# Interface_Voltage_Sensor_1.net
KiCad netlist of a schematic drawn in Altium Designer
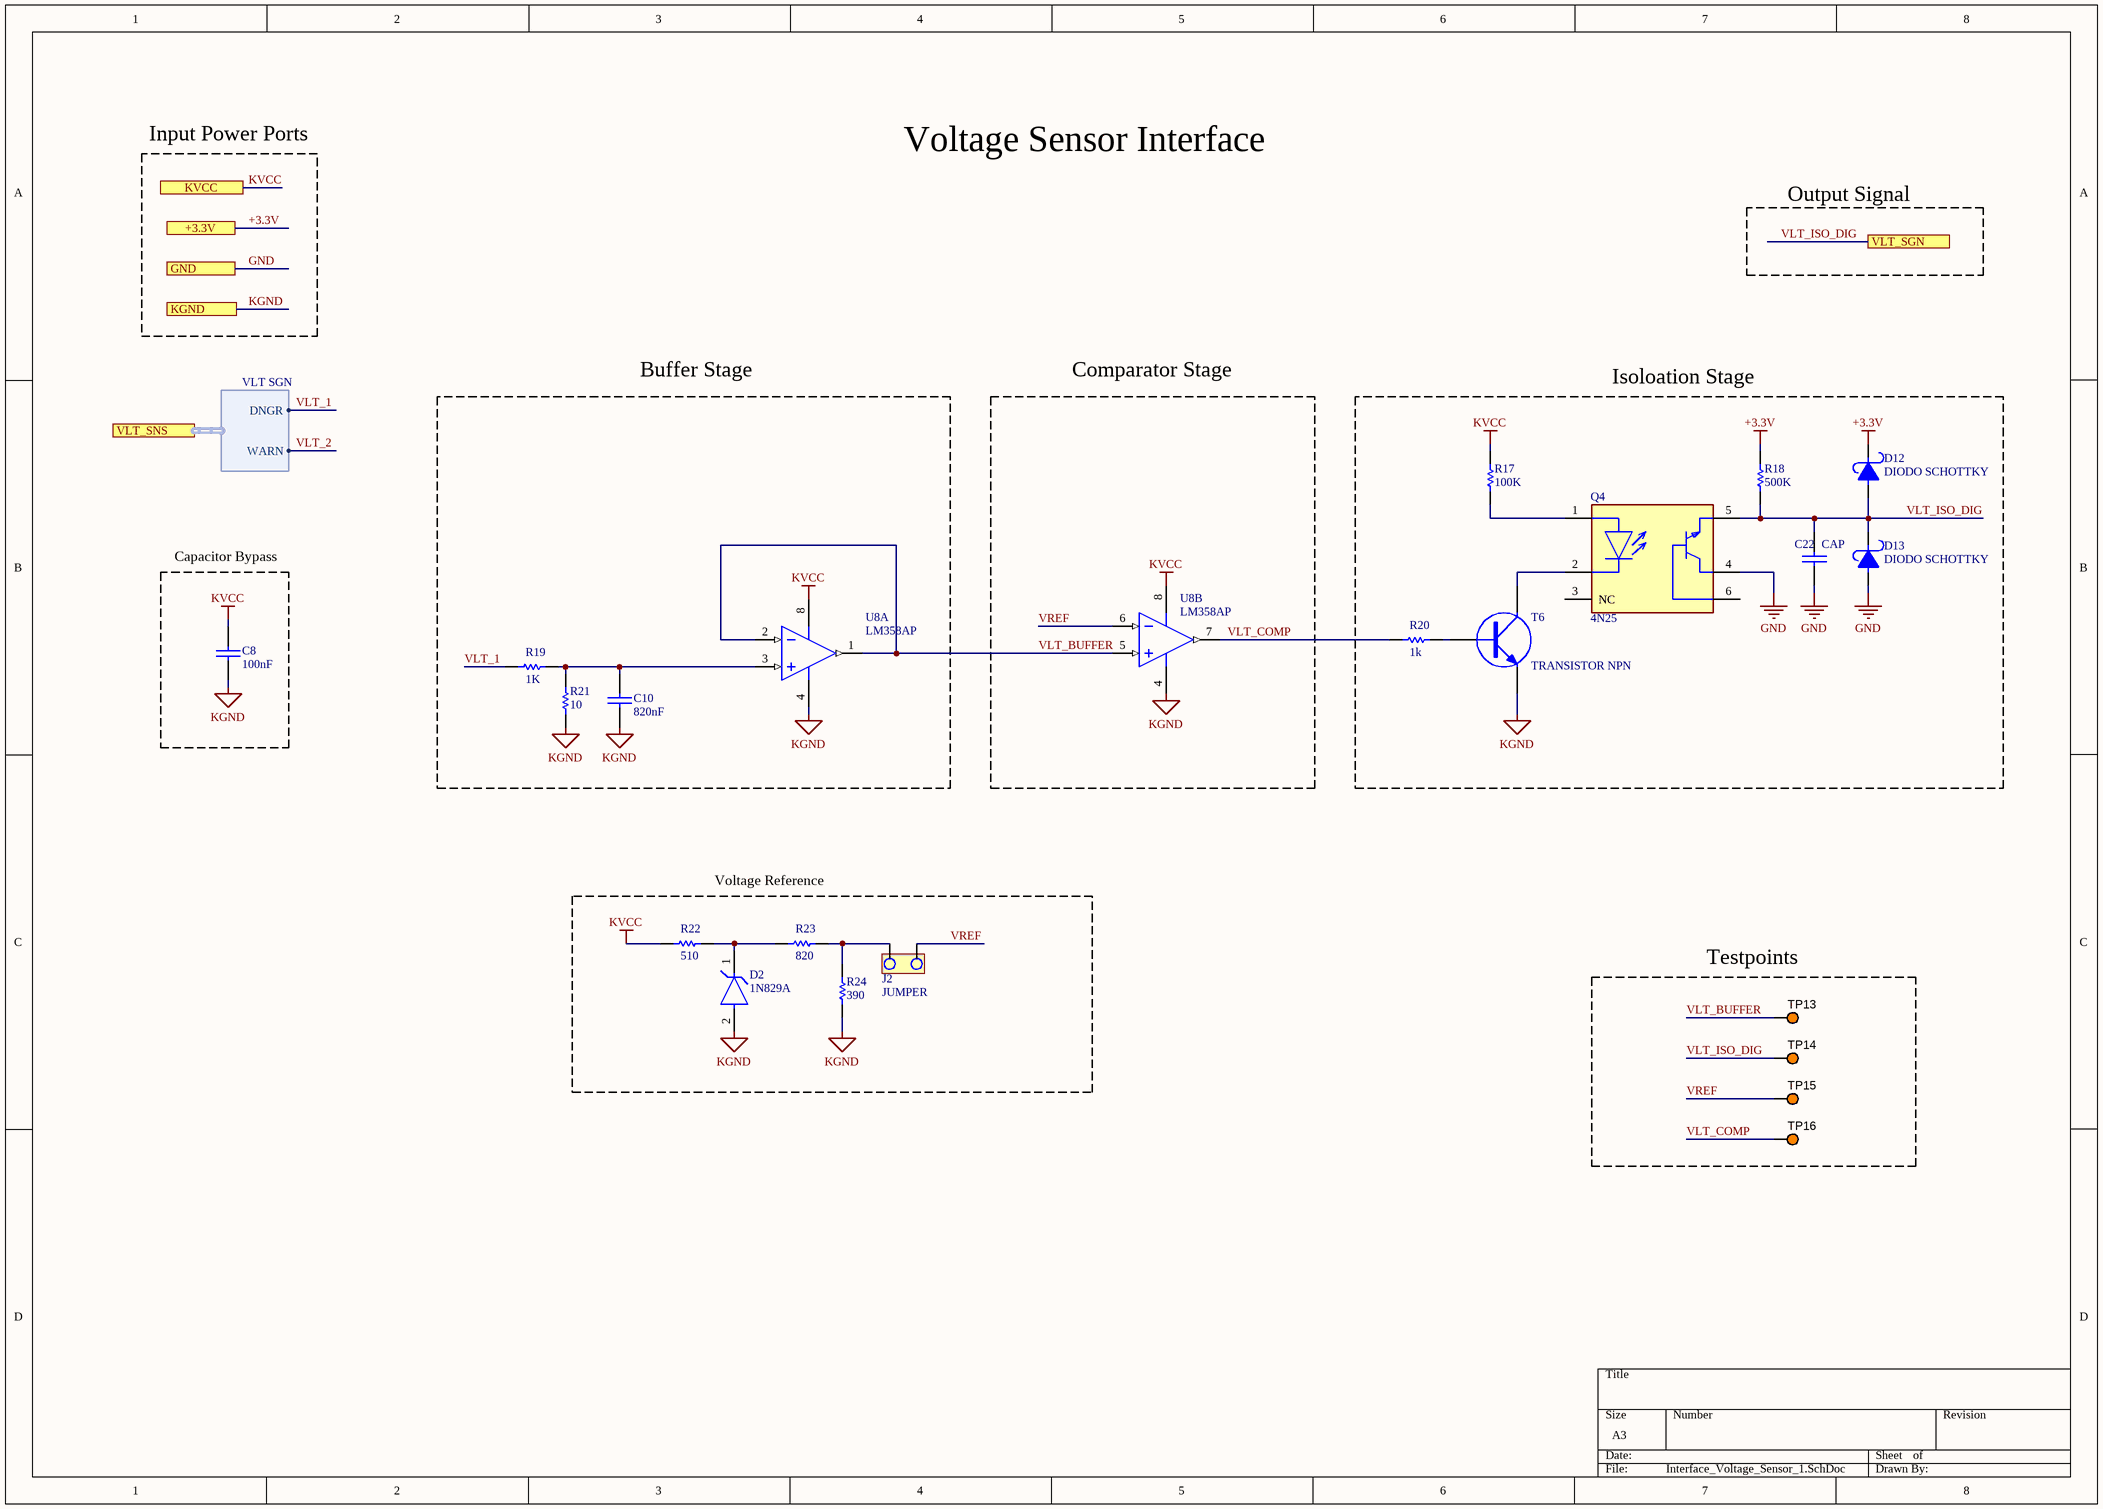
[diagram p0: Interface_Voltage_Sensor_1.SchDoc]

(export (version "E")
  (design (tool "Eeschema 10.0.6"))
  (components
    (comp (ref "C8") (value "100nF") (footprint "CAP200") (libsource (lib "LIBEBAL") (part "CAP")))
    (comp (ref "C10") (value "820nF") (footprint "CAP200") (libsource (lib "LIBEBAL") (part "CAP")))
    (comp (ref "C22") (value "CAP") (footprint "CAP200") (libsource (lib "LIBEBAL") (part "CAP")))
    (comp (ref "D2")
      (value "1N829A")
      (footprint "FP-DO-35-MFG")
      (description "Zener Diode, 6.2V V(Z), 4.84%, 0.5W, Silicon, DO-204AA")
      (libsource (lib "TD") (part "f813f71cba58e380607f5dd3caf9714"))
    )
    (comp (ref "D12")
      (value "DIODO SCHOTTKY")
      (footprint "DO41")
      (libsource (lib "LIBEBAL") (part "DIODO SCHOTTKY"))
    )
    (comp (ref "D13")
      (value "DIODO SCHOTTKY")
      (footprint "DO41")
      (libsource (lib "LIBEBAL") (part "DIODO SCHOTTKY"))
    )
    (comp (ref "J2") (value "JUMPER") (footprint "JUMPER2") (libsource (lib "LIBEBAL") (part "JUMPER")))
    (comp (ref "Q4")
      (value "4N25")
      (footprint "FP-4N25-MFG")
      (description "VISHAY 4N25 Transistor Output Optocoupler, 1 Channel, DIP, 6 Pins, 60 mA, 5 kV, 20 %")
      (libsource (lib "TD") (part "f1df9f29c47de6998195431899ac75d"))
    )
    (comp (ref "R17") (value "100K") (footprint "RES400") (libsource (lib "TD") (part "RES")))
    (comp (ref "R18") (value "500K") (footprint "RES400") (libsource (lib "TD") (part "RES")))
    (comp (ref "R19") (value "1K") (footprint "RES400") (libsource (lib "TD") (part "RES")))
    (comp (ref "R20") (value "1k") (footprint "RES400") (libsource (lib "TD") (part "RES")))
    (comp (ref "R21") (value "10") (footprint "RES400") (libsource (lib "TD") (part "RES")))
    (comp (ref "R22") (value "510") (footprint "RES400") (libsource (lib "TD") (part "RES")))
    (comp (ref "R23") (value "820") (footprint "RES400") (libsource (lib "TD") (part "RES")))
    (comp (ref "R24") (value "390") (footprint "RES400") (libsource (lib "TD") (part "RES")))
    (comp (ref "T6")
      (value "TRANSISTOR NPN")
      (footprint "TO92")
      (libsource (lib "TD") (part "TRANSISTOR NPN"))
    )
    (comp (ref "TP13")
      (value "5003")
      (footprint "KSTN-5003")
      (description "Test Point, Orange, Height 4.6 mm, Tail Length 3 mm, 1-Pin THD, RoHS")
      (fields (field (name "MANUFACTURER") "Keystone"))
      (libsource (lib "TD") (part "TESTPOINT_ORANGE"))
    )
    (comp (ref "TP14")
      (value "5003")
      (footprint "KSTN-5003")
      (description "Test Point, Orange, Height 4.6 mm, Tail Length 3 mm, 1-Pin THD, RoHS")
      (fields (field (name "MANUFACTURER") "Keystone"))
      (libsource (lib "TD") (part "TESTPOINT_ORANGE"))
    )
    (comp (ref "TP15")
      (value "5003")
      (footprint "KSTN-5003")
      (description "Test Point, Orange, Height 4.6 mm, Tail Length 3 mm, 1-Pin THD, RoHS")
      (fields (field (name "MANUFACTURER") "Keystone"))
      (libsource (lib "TD") (part "TESTPOINT_ORANGE"))
    )
    (comp (ref "TP16")
      (value "5003")
      (footprint "KSTN-5003")
      (description "Test Point, Orange, Height 4.6 mm, Tail Length 3 mm, 1-Pin THD, RoHS")
      (fields (field (name "MANUFACTURER") "Keystone"))
      (libsource (lib "TD") (part "TESTPOINT_ORANGE"))
    )
    (comp (ref "U8")
      (value "LM358AP")
      (footprint "P0008A")
      (description "Dual Operational Amplifier, 3 to 32 V, 0 to 70 degC, 8-Pin PDIP (P), Pb-Free (RoHS), Tube")
      (fields (field (name "MANUFACTURER") "Texas Instruments (TI)"))
      (libsource (lib "TD") (part "TI-LM358-8"))
    )
  )
  (nets
    (net (code "3") (name "+3.3V") (class "Default")
      (node (ref "D12") (pin "2") (pinfunction "2_2") (pintype "passive"))
      (node (ref "R18") (pin "2") (pinfunction "2_2") (pintype "passive"))
    )
    (net (code "5") (name "/VLT_1") (class "Default")
      (node (ref "R19") (pin "1") (pinfunction "1_1") (pintype "passive"))
    )
    (net (code "7") (name "/VLT_BUFFER") (class "Default")
      (node (ref "TP13") (pin "1") (pinfunction "1_1") (pintype "passive"))
      (node (ref "U8") (pin "1") (pinfunction "1OUT_1") (pintype "output"))
      (node (ref "U8") (pin "2") (pinfunction "1IN-_2") (pintype "input"))
      (node (ref "U8") (pin "5") (pinfunction "2IN+_5") (pintype "input"))
    )
    (net (code "8") (name "/VLT_COMP") (class "Default")
      (node (ref "R20") (pin "1") (pinfunction "1_1") (pintype "passive"))
      (node (ref "TP16") (pin "1") (pinfunction "1_1") (pintype "passive"))
      (node (ref "U8") (pin "7") (pinfunction "2OUT_7") (pintype "output"))
    )
    (net (code "9") (name "/VLT_ISO_DIG") (class "Default")
      (node (ref "C22") (pin "1") (pinfunction "1_1") (pintype "passive"))
      (node (ref "D12") (pin "1") (pinfunction "1_1") (pintype "passive"))
      (node (ref "D13") (pin "2") (pinfunction "2_2") (pintype "passive"))
      (node (ref "Q4") (pin "5") (pinfunction "C_5") (pintype "passive"))
      (node (ref "R18") (pin "1") (pinfunction "1_1") (pintype "passive"))
      (node (ref "TP14") (pin "1") (pinfunction "1_1") (pintype "passive"))
    )
    (net (code "10") (name "/VREF") (class "Default")
      (node (ref "J2") (pin "2") (pinfunction "2_2") (pintype "passive"))
      (node (ref "TP15") (pin "1") (pinfunction "1_1") (pintype "passive"))
      (node (ref "U8") (pin "6") (pinfunction "2IN-_6") (pintype "input"))
    )
    (net (code "12") (name "GND") (class "Default")
      (node (ref "C22") (pin "2") (pinfunction "2_2") (pintype "passive"))
      (node (ref "D13") (pin "1") (pinfunction "1_1") (pintype "passive"))
      (node (ref "Q4") (pin "4") (pinfunction "E_4") (pintype "passive"))
    )
    (net (code "13") (name "KGND") (class "Default")
      (node (ref "C10") (pin "2") (pinfunction "2_2") (pintype "passive"))
      (node (ref "C8") (pin "2") (pinfunction "2_2") (pintype "passive"))
      (node (ref "D2") (pin "2") (pinfunction "A_2") (pintype "passive"))
      (node (ref "R21") (pin "1") (pinfunction "1_1") (pintype "passive"))
      (node (ref "R24") (pin "1") (pinfunction "1_1") (pintype "passive"))
      (node (ref "T6") (pin "3") (pinfunction "E_3") (pintype "passive"))
      (node (ref "U8") (pin "4") (pinfunction "GND_4") (pintype "power_in"))
    )
    (net (code "14") (name "KVCC") (class "Default")
      (node (ref "C8") (pin "1") (pinfunction "1_1") (pintype "passive"))
      (node (ref "R17") (pin "2") (pinfunction "2_2") (pintype "passive"))
      (node (ref "R22") (pin "1") (pinfunction "1_1") (pintype "passive"))
      (node (ref "U8") (pin "8") (pinfunction "VCC_8") (pintype "power_in"))
    )
    (net (code "15") (name "Net-(D2-C)") (class "Default")
      (node (ref "D2") (pin "1") (pinfunction "C_1") (pintype "passive"))
      (node (ref "R22") (pin "2") (pinfunction "2_2") (pintype "passive"))
      (node (ref "R23") (pin "1") (pinfunction "1_1") (pintype "passive"))
    )
    (net (code "16") (name "Net-(J2-Pad1)") (class "Default")
      (node (ref "J2") (pin "1") (pinfunction "1_1") (pintype "passive"))
      (node (ref "R23") (pin "2") (pinfunction "2_2") (pintype "passive"))
      (node (ref "R24") (pin "2") (pinfunction "2_2") (pintype "passive"))
    )
    (net (code "17") (name "Net-(Q4-A)") (class "Default")
      (node (ref "Q4") (pin "1") (pinfunction "A_1") (pintype "passive"))
      (node (ref "R17") (pin "1") (pinfunction "1_1") (pintype "passive"))
    )
    (net (code "18") (name "Net-(T6-B)") (class "Default")
      (node (ref "R20") (pin "2") (pinfunction "2_2") (pintype "passive"))
      (node (ref "T6") (pin "1") (pinfunction "B_1") (pintype "passive"))
    )
    (net (code "19") (name "Net-(T6-C)") (class "Default")
      (node (ref "Q4") (pin "2") (pinfunction "C_2") (pintype "passive"))
      (node (ref "T6") (pin "2") (pinfunction "C_2") (pintype "passive"))
    )
    (net (code "20") (name "Net-(U8A-1IN+)") (class "Default")
      (node (ref "C10") (pin "1") (pinfunction "1_1") (pintype "passive"))
      (node (ref "R19") (pin "2") (pinfunction "2_2") (pintype "passive"))
      (node (ref "R21") (pin "2") (pinfunction "2_2") (pintype "passive"))
      (node (ref "U8") (pin "3") (pinfunction "1IN+_3") (pintype "input"))
    )
    (net (code "21") (name "unconnected-(Q4-B-Pad6)") (class "Default")
      (node (ref "Q4") (pin "6") (pinfunction "B_6") (pintype "passive"))
    )
    (net (code "22") (name "unconnected-(Q4-NC-Pad3)") (class "Default")
      (node (ref "Q4") (pin "3") (pinfunction "NC_3") (pintype "passive"))
    )
  )
)
